# atmega_darlington_diodes.net
KiCad netlist of a schematic drawn in Altium Designer
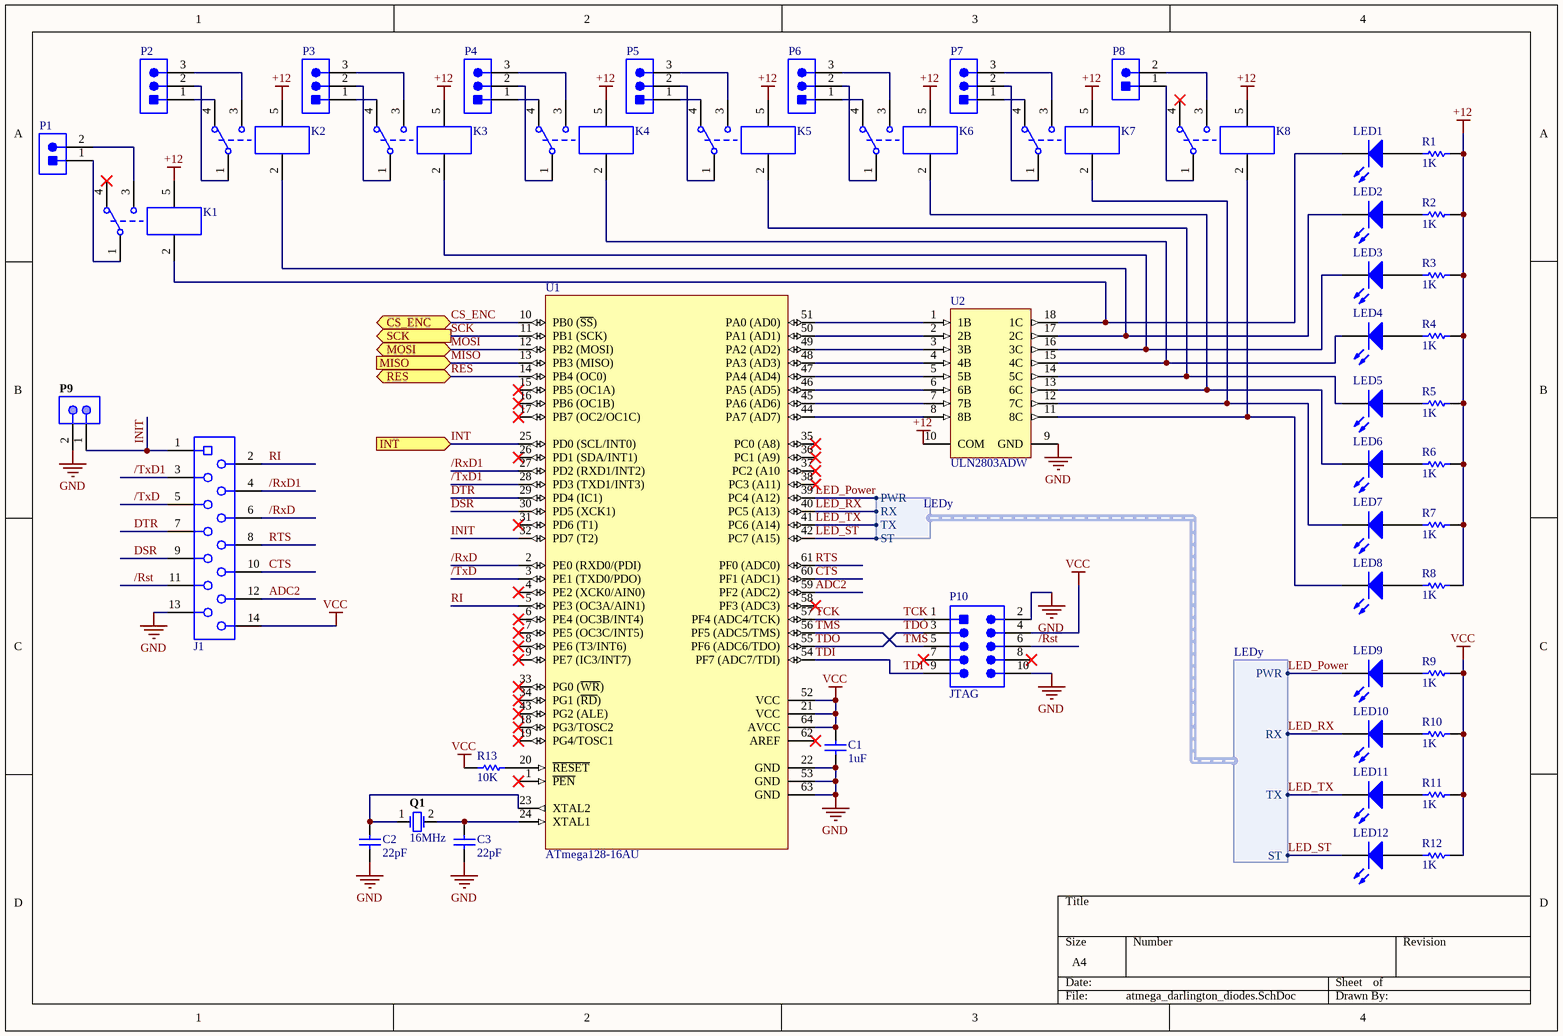
[diagram p0: atmega_darlington_diodes.SchDoc]

(export (version "E")
  (design (tool "Eeschema 10.0.6"))
  (components
    (comp (ref "C1")
      (value "1uF")
      (footprint "CAPC1206(3216)130_L")
      (description "CAP 1uF 10V ±5% 1206 (3216 Metric) Thickness 1.3mm SMD")
      (fields (field (name "TOLERANCE") "Â±5%"))
      (libsource (lib "Altium Content Vault") (part "CAP"))
    )
    (comp (ref "C2")
      (value "22pF")
      (footprint "CAPC1206(3216)100_L")
      (description "CAP 22pF 10V ±0.25pF 1206 (3216 Metric) Thickness 1mm SMD")
      (fields (field (name "TOLERANCE") "Â±0.25pF"))
      (libsource (lib "Altium Content Vault") (part "CAP"))
    )
    (comp (ref "C3")
      (value "22pF")
      (footprint "CAPC1206(3216)100_L")
      (description "CAP 22pF 10V ±0.25pF 1206 (3216 Metric) Thickness 1mm SMD")
      (fields (field (name "TOLERANCE") "Â±0.25pF"))
      (libsource (lib "Altium Content Vault") (part "CAP"))
    )
    (comp (ref "J1")
      (value "490107671412")
      (footprint "490107671412")
      (description "REDFIT IDC SKEDD Connector WR-WST, pitch 2.54 mm, 14 pins")
      (fields (field (name "MANUFACTURER") "Wurth Elektronik") (field (name "PUBLISHER") "WurthElektronik"))
      (libsource (lib "Altium Content Vault") (part "WE-CN-2S-F-R14"))
    )
    (comp (ref "K1")
      (value "JS1-12V")
      (footprint "PNSC-JS1-12V_V")
      (description "Cubic Type 1C Power Relay, SPDT, 10 A, 12 V, -40 to 70 degC, 5-Pin THD, RoHS, Bulk")
      (fields (field (name "MANUFACTURER") "Panasonic") (field (name "APPROVAL BODIES") "UL&CSA,TUV"))
      (libsource (lib "Altium Content Vault") (part "RELAY-SPDT-5_E"))
    )
    (comp (ref "K2")
      (value "JS1-12V")
      (footprint "PNSC-JS1-12V_V")
      (description "Cubic Type 1C Power Relay, SPDT, 10 A, 12 V, -40 to 70 degC, 5-Pin THD, RoHS, Bulk")
      (fields (field (name "MANUFACTURER") "Panasonic") (field (name "APPROVAL BODIES") "UL&CSA,TUV"))
      (libsource (lib "Altium Content Vault") (part "RELAY-SPDT-5_E"))
    )
    (comp (ref "K3")
      (value "JS1-12V")
      (footprint "PNSC-JS1-12V_V")
      (description "Cubic Type 1C Power Relay, SPDT, 10 A, 12 V, -40 to 70 degC, 5-Pin THD, RoHS, Bulk")
      (fields (field (name "MANUFACTURER") "Panasonic") (field (name "APPROVAL BODIES") "UL&CSA,TUV"))
      (libsource (lib "Altium Content Vault") (part "RELAY-SPDT-5_E"))
    )
    (comp (ref "K4")
      (value "JS1-12V")
      (footprint "PNSC-JS1-12V_V")
      (description "Cubic Type 1C Power Relay, SPDT, 10 A, 12 V, -40 to 70 degC, 5-Pin THD, RoHS, Bulk")
      (fields (field (name "MANUFACTURER") "Panasonic") (field (name "APPROVAL BODIES") "UL&CSA,TUV"))
      (libsource (lib "Altium Content Vault") (part "RELAY-SPDT-5_E"))
    )
    (comp (ref "K5")
      (value "JS1-12V")
      (footprint "PNSC-JS1-12V_V")
      (description "Cubic Type 1C Power Relay, SPDT, 10 A, 12 V, -40 to 70 degC, 5-Pin THD, RoHS, Bulk")
      (fields (field (name "MANUFACTURER") "Panasonic") (field (name "APPROVAL BODIES") "UL&CSA,TUV"))
      (libsource (lib "Altium Content Vault") (part "RELAY-SPDT-5_E"))
    )
    (comp (ref "K6")
      (value "JS1-12V")
      (footprint "PNSC-JS1-12V_V")
      (description "Cubic Type 1C Power Relay, SPDT, 10 A, 12 V, -40 to 70 degC, 5-Pin THD, RoHS, Bulk")
      (fields (field (name "MANUFACTURER") "Panasonic") (field (name "APPROVAL BODIES") "UL&CSA,TUV"))
      (libsource (lib "Altium Content Vault") (part "RELAY-SPDT-5_E"))
    )
    (comp (ref "K7")
      (value "JS1-12V")
      (footprint "PNSC-JS1-12V_V")
      (description "Cubic Type 1C Power Relay, SPDT, 10 A, 12 V, -40 to 70 degC, 5-Pin THD, RoHS, Bulk")
      (fields (field (name "MANUFACTURER") "Panasonic") (field (name "APPROVAL BODIES") "UL&CSA,TUV"))
      (libsource (lib "Altium Content Vault") (part "RELAY-SPDT-5_E"))
    )
    (comp (ref "K8")
      (value "JS1-12V")
      (footprint "PNSC-JS1-12V_V")
      (description "Cubic Type 1C Power Relay, SPDT, 10 A, 12 V, -40 to 70 degC, 5-Pin THD, RoHS, Bulk")
      (fields (field (name "MANUFACTURER") "Panasonic") (field (name "APPROVAL BODIES") "UL&CSA,TUV"))
      (libsource (lib "Altium Content Vault") (part "RELAY-SPDT-5_E"))
    )
    (comp (ref "LED1")
      (value "150120YS75000")
      (footprint "1206_A")
      (description "SMD mono-color Chip LED, WL-SMCW, Yellow")
      (fields (field (name "MANUFACTURER") "Wuerth Elektronik"))
      (libsource (lib "Altium Content Vault") (part "WE-LED_K1A2-2"))
    )
    (comp (ref "LED2")
      (value "150120YS75000")
      (footprint "1206_A")
      (description "SMD mono-color Chip LED, WL-SMCW, Yellow")
      (fields (field (name "MANUFACTURER") "Wuerth Elektronik"))
      (libsource (lib "Altium Content Vault") (part "WE-LED_K1A2-2"))
    )
    (comp (ref "LED3")
      (value "150120YS75000")
      (footprint "1206_A")
      (description "SMD mono-color Chip LED, WL-SMCW, Yellow")
      (fields (field (name "MANUFACTURER") "Wuerth Elektronik"))
      (libsource (lib "Altium Content Vault") (part "WE-LED_K1A2-2"))
    )
    (comp (ref "LED4")
      (value "150120YS75000")
      (footprint "1206_A")
      (description "SMD mono-color Chip LED, WL-SMCW, Yellow")
      (fields (field (name "MANUFACTURER") "Wuerth Elektronik"))
      (libsource (lib "Altium Content Vault") (part "WE-LED_K1A2-2"))
    )
    (comp (ref "LED5")
      (value "150120YS75000")
      (footprint "1206_A")
      (description "SMD mono-color Chip LED, WL-SMCW, Yellow")
      (fields (field (name "MANUFACTURER") "Wuerth Elektronik"))
      (libsource (lib "Altium Content Vault") (part "WE-LED_K1A2-2"))
    )
    (comp (ref "LED6")
      (value "150120YS75000")
      (footprint "1206_A")
      (description "SMD mono-color Chip LED, WL-SMCW, Yellow")
      (fields (field (name "MANUFACTURER") "Wuerth Elektronik"))
      (libsource (lib "Altium Content Vault") (part "WE-LED_K1A2-2"))
    )
    (comp (ref "LED7")
      (value "150120YS75000")
      (footprint "1206_A")
      (description "SMD mono-color Chip LED, WL-SMCW, Yellow")
      (fields (field (name "MANUFACTURER") "Wuerth Elektronik"))
      (libsource (lib "Altium Content Vault") (part "WE-LED_K1A2-2"))
    )
    (comp (ref "LED8")
      (value "150120YS75000")
      (footprint "1206_A")
      (description "SMD mono-color Chip LED, WL-SMCW, Yellow")
      (fields (field (name "MANUFACTURER") "Wuerth Elektronik"))
      (libsource (lib "Altium Content Vault") (part "WE-LED_K1A2-2"))
    )
    (comp (ref "LED9")
      (value "150120BS75000")
      (footprint "1206_A")
      (description "SMD mono-color Chip LED, WL-SMCW, Blue")
      (fields (field (name "MANUFACTURER") "Wuerth Elektronik"))
      (libsource (lib "Altium Content Vault") (part "WE-LED_K1A2-2"))
    )
    (comp (ref "LED10")
      (value "150120GS75000")
      (footprint "1206_A")
      (description "SMD mono-color Chip LED, WL-SMCW, Green")
      (fields (field (name "MANUFACTURER") "Wuerth Elektronik"))
      (libsource (lib "Altium Content Vault") (part "WE-LED_K1A2-2"))
    )
    (comp (ref "LED11")
      (value "150120YS75000")
      (footprint "1206_A")
      (description "SMD mono-color Chip LED, WL-SMCW, Yellow")
      (fields (field (name "MANUFACTURER") "Wuerth Elektronik"))
      (libsource (lib "Altium Content Vault") (part "WE-LED_K1A2-2"))
    )
    (comp (ref "LED12")
      (value "150120RS75000")
      (footprint "1206_A")
      (description "SMD mono-color Chip LED, WL-SMCW, Red")
      (fields (field (name "MANUFACTURER") "Wuerth Elektronik"))
      (libsource (lib "Altium Content Vault") (part "WE-LED_K1A2-2"))
    )
    (comp (ref "P1")
      (value "SCREW-5.0/5.08 2WAYS")
      (footprint "SCREW-5.0-2WAYS_V")
      (description "Socket, Screw Terminal Block, 2 Way, 5.0 mm Pitch, 90 Degree Angle, Through-Hole")
      (fields (field (name "MANUFACTURER") "No Vendor"))
      (libsource (lib "Altium Content Vault") (part "SCREW-2WAYS"))
    )
    (comp (ref "P2")
      (value "SCREW-5.0/5.08 3WAYS")
      (footprint "SCREW-5.0-3WAYS_V")
      (description "Socket, Screw Terminal Block, 3 Way, 5.0 mm Pitch, 90 Degree Angle, Through-Hole")
      (fields (field (name "MANUFACTURER") "No Vendor"))
      (libsource (lib "Altium Content Vault") (part "SCREW-3WAYS"))
    )
    (comp (ref "P3")
      (value "SCREW-5.0/5.08 3WAYS")
      (footprint "SCREW-5.0-3WAYS_V")
      (description "Socket, Screw Terminal Block, 3 Way, 5.0 mm Pitch, 90 Degree Angle, Through-Hole")
      (fields (field (name "MANUFACTURER") "No Vendor"))
      (libsource (lib "Altium Content Vault") (part "SCREW-3WAYS"))
    )
    (comp (ref "P4")
      (value "SCREW-5.0/5.08 3WAYS")
      (footprint "SCREW-5.0-3WAYS_V")
      (description "Socket, Screw Terminal Block, 3 Way, 5.0 mm Pitch, 90 Degree Angle, Through-Hole")
      (fields (field (name "MANUFACTURER") "No Vendor"))
      (libsource (lib "Altium Content Vault") (part "SCREW-3WAYS"))
    )
    (comp (ref "P5")
      (value "SCREW-5.0/5.08 3WAYS")
      (footprint "SCREW-5.0-3WAYS_V")
      (description "Socket, Screw Terminal Block, 3 Way, 5.0 mm Pitch, 90 Degree Angle, Through-Hole")
      (fields (field (name "MANUFACTURER") "No Vendor"))
      (libsource (lib "Altium Content Vault") (part "SCREW-3WAYS"))
    )
    (comp (ref "P6")
      (value "SCREW-5.0/5.08 3WAYS")
      (footprint "SCREW-5.0-3WAYS_V")
      (description "Socket, Screw Terminal Block, 3 Way, 5.0 mm Pitch, 90 Degree Angle, Through-Hole")
      (fields (field (name "MANUFACTURER") "No Vendor"))
      (libsource (lib "Altium Content Vault") (part "SCREW-3WAYS"))
    )
    (comp (ref "P7")
      (value "SCREW-5.0/5.08 3WAYS")
      (footprint "SCREW-5.0-3WAYS_V")
      (description "Socket, Screw Terminal Block, 3 Way, 5.0 mm Pitch, 90 Degree Angle, Through-Hole")
      (fields (field (name "MANUFACTURER") "No Vendor"))
      (libsource (lib "Altium Content Vault") (part "SCREW-3WAYS"))
    )
    (comp (ref "P8")
      (value "SCREW-5.0/5.08 2WAYS")
      (footprint "SCREW-5.0-2WAYS_V")
      (description "Socket, Screw Terminal Block, 2 Way, 5.0 mm Pitch, 90 Degree Angle, Through-Hole")
      (fields (field (name "MANUFACTURER") "No Vendor"))
      (libsource (lib "Altium Content Vault") (part "SCREW-2WAYS"))
    )
    (comp (ref "P9")
      (value "PH2541-2-SPGRH-6-3")
      (footprint "PH2541-2-SPGRH-6-3_V")
      (description "Male Header, Pitch 2.54mm, 2x1 Position, Mated Height 6mm, Tail Length 3mm")
      (libsource (lib "Altium Content Vault") (part "PCE-HDR-1P-M-R2"))
    )
    (comp (ref "P10")
      (value "JTAG")
      (footprint "3M-2510-6002_V")
      (fields (field (name "MANUFACTURER") "3M"))
      (libsource (lib "Altium Content Vault") (part "CN-2P-M-R10"))
    )
    (comp (ref "Q1")
      (value "16MHz")
      (footprint "JPY-HC-49US")
      (description "Crystal, 16 MHz, +/- 30 ppm, 18 pF, -20 to 70 degC, 2-Pin THD")
      (fields (field (name "MANUFACTURER") "Jing peng yuan"))
      (libsource (lib "Altium Content Vault") (part "XTAL-1-2-2"))
    )
    (comp (ref "R1")
      (value "1K")
      (footprint "RESC1206(3216)_L")
      (description "1K 0.25W 1% 1206 (3216 Metric)  SMD")
      (fields (field (name "POWER") "0.25 W") (field (name "TOLERANCE") "1 %"))
      (libsource (lib "Altium Content Vault") (part "RES"))
    )
    (comp (ref "R2")
      (value "1K")
      (footprint "RESC1206(3216)_L")
      (description "1K 0.25W 1% 1206 (3216 Metric)  SMD")
      (fields (field (name "POWER") "0.25 W") (field (name "TOLERANCE") "1 %"))
      (libsource (lib "Altium Content Vault") (part "RES"))
    )
    (comp (ref "R3")
      (value "1K")
      (footprint "RESC1206(3216)_L")
      (description "1K 0.25W 1% 1206 (3216 Metric)  SMD")
      (fields (field (name "POWER") "0.25 W") (field (name "TOLERANCE") "1 %"))
      (libsource (lib "Altium Content Vault") (part "RES"))
    )
    (comp (ref "R4")
      (value "1K")
      (footprint "RESC1206(3216)_L")
      (description "1K 0.25W 1% 1206 (3216 Metric)  SMD")
      (fields (field (name "POWER") "0.25 W") (field (name "TOLERANCE") "1 %"))
      (libsource (lib "Altium Content Vault") (part "RES"))
    )
    (comp (ref "R5")
      (value "1K")
      (footprint "RESC1206(3216)_L")
      (description "1K 0.25W 1% 1206 (3216 Metric)  SMD")
      (fields (field (name "POWER") "0.25 W") (field (name "TOLERANCE") "1 %"))
      (libsource (lib "Altium Content Vault") (part "RES"))
    )
    (comp (ref "R6")
      (value "1K")
      (footprint "RESC1206(3216)_L")
      (description "1K 0.25W 1% 1206 (3216 Metric)  SMD")
      (fields (field (name "POWER") "0.25 W") (field (name "TOLERANCE") "1 %"))
      (libsource (lib "Altium Content Vault") (part "RES"))
    )
    (comp (ref "R7")
      (value "1K")
      (footprint "RESC1206(3216)_L")
      (description "1K 0.25W 1% 1206 (3216 Metric)  SMD")
      (fields (field (name "POWER") "0.25 W") (field (name "TOLERANCE") "1 %"))
      (libsource (lib "Altium Content Vault") (part "RES"))
    )
    (comp (ref "R8")
      (value "1K")
      (footprint "RESC1206(3216)_L")
      (description "1K 0.25W 1% 1206 (3216 Metric)  SMD")
      (fields (field (name "POWER") "0.25 W") (field (name "TOLERANCE") "1 %"))
      (libsource (lib "Altium Content Vault") (part "RES"))
    )
    (comp (ref "R9")
      (value "1K")
      (footprint "RESC1206(3216)_L")
      (description "1K 0.25W 1% 1206 (3216 Metric)  SMD")
      (fields (field (name "POWER") "0.25 W") (field (name "TOLERANCE") "1 %"))
      (libsource (lib "Altium Content Vault") (part "RES"))
    )
    (comp (ref "R10")
      (value "1K")
      (footprint "RESC1206(3216)_L")
      (description "1K 0.25W 1% 1206 (3216 Metric)  SMD")
      (fields (field (name "POWER") "0.25 W") (field (name "TOLERANCE") "1 %"))
      (libsource (lib "Altium Content Vault") (part "RES"))
    )
    (comp (ref "R11")
      (value "1K")
      (footprint "RESC1206(3216)_L")
      (description "1K 0.25W 1% 1206 (3216 Metric)  SMD")
      (fields (field (name "POWER") "0.25 W") (field (name "TOLERANCE") "1 %"))
      (libsource (lib "Altium Content Vault") (part "RES"))
    )
    (comp (ref "R12")
      (value "1K")
      (footprint "RESC1206(3216)_L")
      (description "1K 0.25W 1% 1206 (3216 Metric)  SMD")
      (fields (field (name "POWER") "0.25 W") (field (name "TOLERANCE") "1 %"))
      (libsource (lib "Altium Content Vault") (part "RES"))
    )
    (comp (ref "R13")
      (value "10K")
      (footprint "RESC1206(3216)_L")
      (description "10K 0.25W 1% 1206 (3216 Metric)  SMD")
      (fields (field (name "POWER") "0.25 W") (field (name "TOLERANCE") "1 %"))
      (libsource (lib "Altium Content Vault") (part "RES"))
    )
    (comp (ref "U1")
      (value "ATmega128-16AU")
      (footprint "64A_L")
      (libsource (lib "Altium Content Vault") (part "MC-8B-AT64-SQ64"))
    )
    (comp (ref "U2")
      (value "ULN2803ADW")
      (footprint "DW0018A_L")
      (fields (field (name "MANUFACTURER") "Texas Instruments"))
      (libsource (lib "Altium Content Vault") (part "TI-ULN2803A-SOIC_DW-18"))
    )
  )
  (nets
    (net (code "2") (name "+12") (class "Default")
      (node (ref "K1") (pin "5") (pinfunction "5_5") (pintype "passive"))
      (node (ref "K2") (pin "5") (pinfunction "5_5") (pintype "passive"))
      (node (ref "K3") (pin "5") (pinfunction "5_5") (pintype "passive"))
      (node (ref "K4") (pin "5") (pinfunction "5_5") (pintype "passive"))
      (node (ref "K5") (pin "5") (pinfunction "5_5") (pintype "passive"))
      (node (ref "K6") (pin "5") (pinfunction "5_5") (pintype "passive"))
      (node (ref "K7") (pin "5") (pinfunction "5_5") (pintype "passive"))
      (node (ref "K8") (pin "5") (pinfunction "5_5") (pintype "passive"))
      (node (ref "R1") (pin "2") (pinfunction "2_2") (pintype "passive"))
      (node (ref "R2") (pin "2") (pinfunction "2_2") (pintype "passive"))
      (node (ref "R3") (pin "2") (pinfunction "2_2") (pintype "passive"))
      (node (ref "R4") (pin "2") (pinfunction "2_2") (pintype "passive"))
      (node (ref "R5") (pin "2") (pinfunction "2_2") (pintype "passive"))
      (node (ref "R6") (pin "2") (pinfunction "2_2") (pintype "passive"))
      (node (ref "R7") (pin "2") (pinfunction "2_2") (pintype "passive"))
      (node (ref "R8") (pin "2") (pinfunction "2_2") (pintype "passive"))
      (node (ref "U2") (pin "10") (pinfunction "COM_10") (pintype "passive"))
    )
    (net (code "3") (name "/ADC2") (class "Default")
      (node (ref "J1") (pin "12") (pinfunction "12_12") (pintype "passive"))
      (node (ref "U1") (pin "59") (pinfunction "PF2_(ADC2)_59") (pintype "bidirectional"))
    )
    (net (code "4") (name "/CS_ENC") (class "Default")
      (node (ref "U1") (pin "10") (pinfunction "PB0_(~{SS})_10") (pintype "bidirectional"))
    )
    (net (code "5") (name "/CTS") (class "Default")
      (node (ref "J1") (pin "10") (pinfunction "10_10") (pintype "passive"))
      (node (ref "U1") (pin "60") (pinfunction "PF1_(ADC1)_60") (pintype "bidirectional"))
    )
    (net (code "6") (name "/DSR") (class "Default")
      (node (ref "J1") (pin "9") (pinfunction "9_9") (pintype "passive"))
      (node (ref "U1") (pin "30") (pinfunction "PD5_(XCK1)_30") (pintype "bidirectional"))
    )
    (net (code "7") (name "/DTR") (class "Default")
      (node (ref "J1") (pin "7") (pinfunction "7_7") (pintype "passive"))
      (node (ref "U1") (pin "29") (pinfunction "PD4_(IC1)_29") (pintype "bidirectional"))
    )
    (net (code "8") (name "/INIT") (class "Default")
      (node (ref "J1") (pin "1") (pinfunction "1_1") (pintype "passive"))
      (node (ref "P9") (pin "1") (pinfunction "1_1") (pintype "passive"))
      (node (ref "U1") (pin "32") (pinfunction "PD7_(T2)_32") (pintype "bidirectional"))
    )
    (net (code "9") (name "/INT") (class "Default")
      (node (ref "U1") (pin "25") (pinfunction "PD0_(SCL/INT0)_25") (pintype "bidirectional"))
    )
    (net (code "10") (name "/LED_Power") (class "Default")
      (node (ref "LED9") (pin "1") (pinfunction "K_1") (pintype "passive"))
      (node (ref "U1") (pin "39") (pinfunction "PC4_(A12)_39") (pintype "bidirectional"))
    )
    (net (code "11") (name "/LED_RX") (class "Default")
      (node (ref "LED10") (pin "1") (pinfunction "K_1") (pintype "passive"))
      (node (ref "U1") (pin "40") (pinfunction "PC5_(A13)_40") (pintype "bidirectional"))
    )
    (net (code "12") (name "/LED_ST") (class "Default")
      (node (ref "LED12") (pin "1") (pinfunction "K_1") (pintype "passive"))
      (node (ref "U1") (pin "42") (pinfunction "PC7_(A15)_42") (pintype "bidirectional"))
    )
    (net (code "13") (name "/LED_TX") (class "Default")
      (node (ref "LED11") (pin "1") (pinfunction "K_1") (pintype "passive"))
      (node (ref "U1") (pin "41") (pinfunction "PC6_(A14)_41") (pintype "bidirectional"))
    )
    (net (code "14") (name "/MISO") (class "Default")
      (node (ref "U1") (pin "13") (pinfunction "PB3_(MISO)_13") (pintype "bidirectional"))
    )
    (net (code "15") (name "/MOSI") (class "Default")
      (node (ref "U1") (pin "12") (pinfunction "PB2_(MOSI)_12") (pintype "bidirectional"))
    )
    (net (code "16") (name "/RES") (class "Default")
      (node (ref "U1") (pin "14") (pinfunction "PB4_(OC0)_14") (pintype "bidirectional"))
    )
    (net (code "17") (name "/RI") (class "Default")
      (node (ref "J1") (pin "2") (pinfunction "2_2") (pintype "passive"))
      (node (ref "U1") (pin "5") (pinfunction "PE3_(OC3A/AIN1)_5") (pintype "bidirectional"))
    )
    (net (code "18") (name "/RTS") (class "Default")
      (node (ref "J1") (pin "8") (pinfunction "8_8") (pintype "passive"))
      (node (ref "U1") (pin "61") (pinfunction "PF0_(ADC0)_61") (pintype "bidirectional"))
    )
    (net (code "19") (name "/SCK") (class "Default")
      (node (ref "U1") (pin "11") (pinfunction "PB1_(SCK)_11") (pintype "bidirectional"))
    )
    (net (code "20") (name "/TCK") (class "Default")
      (node (ref "P10") (pin "1") (pinfunction "1_1") (pintype "passive"))
      (node (ref "U1") (pin "57") (pinfunction "PF4_(ADC4/TCK)_57") (pintype "bidirectional"))
    )
    (net (code "21") (name "/TDI") (class "Default")
      (node (ref "P10") (pin "9") (pinfunction "9_9") (pintype "passive"))
      (node (ref "U1") (pin "54") (pinfunction "PF7_(ADC7/TDI)_54") (pintype "bidirectional"))
    )
    (net (code "22") (name "/TDO") (class "Default")
      (node (ref "P10") (pin "3") (pinfunction "3_3") (pintype "passive"))
      (node (ref "U1") (pin "55") (pinfunction "PF6_(ADC6/TDO)_55") (pintype "bidirectional"))
    )
    (net (code "23") (name "/TMS") (class "Default")
      (node (ref "P10") (pin "5") (pinfunction "5_5") (pintype "passive"))
      (node (ref "U1") (pin "56") (pinfunction "PF5_(ADC5/TMS)_56") (pintype "bidirectional"))
    )
    (net (code "25") (name "/{slash}Rst") (class "Default")
      (node (ref "J1") (pin "11") (pinfunction "11_11") (pintype "passive"))
      (node (ref "P10") (pin "6") (pinfunction "6_6") (pintype "passive"))
    )
    (net (code "26") (name "/{slash}RxD") (class "Default")
      (node (ref "J1") (pin "6") (pinfunction "6_6") (pintype "passive"))
      (node (ref "U1") (pin "2") (pinfunction "PE0_(RXD0/(PDI)_2") (pintype "bidirectional"))
    )
    (net (code "27") (name "/{slash}RxD1") (class "Default")
      (node (ref "J1") (pin "4") (pinfunction "4_4") (pintype "passive"))
      (node (ref "U1") (pin "27") (pinfunction "PD2_(RXD1/INT2)_27") (pintype "bidirectional"))
    )
    (net (code "28") (name "/{slash}TxD") (class "Default")
      (node (ref "J1") (pin "5") (pinfunction "5_5") (pintype "passive"))
      (node (ref "U1") (pin "3") (pinfunction "PE1_(TXD0/PDO)_3") (pintype "bidirectional"))
    )
    (net (code "29") (name "/{slash}TxD1") (class "Default")
      (node (ref "J1") (pin "3") (pinfunction "3_3") (pintype "passive"))
      (node (ref "U1") (pin "28") (pinfunction "PD3_(TXD1/INT3)_28") (pintype "bidirectional"))
    )
    (net (code "30") (name "GND") (class "Default")
      (node (ref "C1") (pin "1") (pinfunction "1_1") (pintype "passive"))
      (node (ref "C2") (pin "1") (pinfunction "1_1") (pintype "passive"))
      (node (ref "C3") (pin "1") (pinfunction "1_1") (pintype "passive"))
      (node (ref "J1") (pin "13") (pinfunction "13_13") (pintype "passive"))
      (node (ref "P10") (pin "10") (pinfunction "10_10") (pintype "passive"))
      (node (ref "P10") (pin "2") (pinfunction "2_2") (pintype "passive"))
      (node (ref "P9") (pin "2") (pinfunction "2_2") (pintype "passive"))
      (node (ref "U1") (pin "22") (pinfunction "GND_22") (pintype "power_in"))
      (node (ref "U1") (pin "53") (pinfunction "GND_53") (pintype "power_in"))
      (node (ref "U1") (pin "63") (pinfunction "GND_63") (pintype "power_in"))
      (node (ref "U2") (pin "9") (pinfunction "GND_9") (pintype "power_in"))
    )
    (net (code "31") (name "Net-(K1-COM)") (class "Default")
      (node (ref "K1") (pin "1") (pinfunction "COM_1") (pintype "passive"))
      (node (ref "P1") (pin "1") (pinfunction "1_1") (pintype "passive"))
    )
    (net (code "32") (name "Net-(K1-N.O.)") (class "Default")
      (node (ref "K1") (pin "3") (pinfunction "N.O._3") (pintype "passive"))
      (node (ref "P1") (pin "2") (pinfunction "2_2") (pintype "passive"))
    )
    (net (code "33") (name "Net-(K2-COM)") (class "Default")
      (node (ref "K2") (pin "1") (pinfunction "COM_1") (pintype "passive"))
      (node (ref "P2") (pin "2") (pinfunction "2_2") (pintype "passive"))
    )
    (net (code "34") (name "Net-(K2-N.C.)") (class "Default")
      (node (ref "K2") (pin "4") (pinfunction "N.C._4") (pintype "passive"))
      (node (ref "P2") (pin "1") (pinfunction "1_1") (pintype "passive"))
    )
    (net (code "35") (name "Net-(K2-N.O.)") (class "Default")
      (node (ref "K2") (pin "3") (pinfunction "N.O._3") (pintype "passive"))
      (node (ref "P2") (pin "3") (pinfunction "3_3") (pintype "passive"))
    )
    (net (code "36") (name "Net-(K3-COM)") (class "Default")
      (node (ref "K3") (pin "1") (pinfunction "COM_1") (pintype "passive"))
      (node (ref "P3") (pin "2") (pinfunction "2_2") (pintype "passive"))
    )
    (net (code "37") (name "Net-(K3-N.C.)") (class "Default")
      (node (ref "K3") (pin "4") (pinfunction "N.C._4") (pintype "passive"))
      (node (ref "P3") (pin "1") (pinfunction "1_1") (pintype "passive"))
    )
    (net (code "38") (name "Net-(K3-N.O.)") (class "Default")
      (node (ref "K3") (pin "3") (pinfunction "N.O._3") (pintype "passive"))
      (node (ref "P3") (pin "3") (pinfunction "3_3") (pintype "passive"))
    )
    (net (code "39") (name "Net-(K4-COM)") (class "Default")
      (node (ref "K4") (pin "1") (pinfunction "COM_1") (pintype "passive"))
      (node (ref "P4") (pin "2") (pinfunction "2_2") (pintype "passive"))
    )
    (net (code "40") (name "Net-(K4-N.C.)") (class "Default")
      (node (ref "K4") (pin "4") (pinfunction "N.C._4") (pintype "passive"))
      (node (ref "P4") (pin "1") (pinfunction "1_1") (pintype "passive"))
    )
    (net (code "41") (name "Net-(K4-N.O.)") (class "Default")
      (node (ref "K4") (pin "3") (pinfunction "N.O._3") (pintype "passive"))
      (node (ref "P4") (pin "3") (pinfunction "3_3") (pintype "passive"))
    )
    (net (code "42") (name "Net-(K5-COM)") (class "Default")
      (node (ref "K5") (pin "1") (pinfunction "COM_1") (pintype "passive"))
      (node (ref "P5") (pin "2") (pinfunction "2_2") (pintype "passive"))
    )
    (net (code "43") (name "Net-(K5-N.C.)") (class "Default")
      (node (ref "K5") (pin "4") (pinfunction "N.C._4") (pintype "passive"))
      (node (ref "P5") (pin "1") (pinfunction "1_1") (pintype "passive"))
    )
    (net (code "44") (name "Net-(K5-N.O.)") (class "Default")
      (node (ref "K5") (pin "3") (pinfunction "N.O._3") (pintype "passive"))
      (node (ref "P5") (pin "3") (pinfunction "3_3") (pintype "passive"))
    )
    (net (code "45") (name "Net-(K6-COM)") (class "Default")
      (node (ref "K6") (pin "1") (pinfunction "COM_1") (pintype "passive"))
      (node (ref "P6") (pin "2") (pinfunction "2_2") (pintype "passive"))
    )
    (net (code "46") (name "Net-(K6-N.C.)") (class "Default")
      (node (ref "K6") (pin "4") (pinfunction "N.C._4") (pintype "passive"))
      (node (ref "P6") (pin "1") (pinfunction "1_1") (pintype "passive"))
    )
    (net (code "47") (name "Net-(K6-N.O.)") (class "Default")
      (node (ref "K6") (pin "3") (pinfunction "N.O._3") (pintype "passive"))
      (node (ref "P6") (pin "3") (pinfunction "3_3") (pintype "passive"))
    )
    (net (code "48") (name "Net-(K7-COM)") (class "Default")
      (node (ref "K7") (pin "1") (pinfunction "COM_1") (pintype "passive"))
      (node (ref "P7") (pin "2") (pinfunction "2_2") (pintype "passive"))
    )
    (net (code "49") (name "Net-(K7-N.C.)") (class "Default")
      (node (ref "K7") (pin "4") (pinfunction "N.C._4") (pintype "passive"))
      (node (ref "P7") (pin "1") (pinfunction "1_1") (pintype "passive"))
    )
    (net (code "50") (name "Net-(K7-N.O.)") (class "Default")
      (node (ref "K7") (pin "3") (pinfunction "N.O._3") (pintype "passive"))
      (node (ref "P7") (pin "3") (pinfunction "3_3") (pintype "passive"))
    )
    (net (code "51") (name "Net-(K8-COM)") (class "Default")
      (node (ref "K8") (pin "1") (pinfunction "COM_1") (pintype "passive"))
      (node (ref "P8") (pin "1") (pinfunction "1_1") (pintype "passive"))
    )
    (net (code "52") (name "Net-(K8-N.O.)") (class "Default")
      (node (ref "K8") (pin "3") (pinfunction "N.O._3") (pintype "passive"))
      (node (ref "P8") (pin "2") (pinfunction "2_2") (pintype "passive"))
    )
    (net (code "53") (name "Net-(LED1-A)") (class "Default")
      (node (ref "LED1") (pin "2") (pinfunction "A_2") (pintype "passive"))
      (node (ref "R1") (pin "1") (pinfunction "1_1") (pintype "passive"))
    )
    (net (code "54") (name "Net-(LED1-K)") (class "Default")
      (node (ref "K1") (pin "2") (pinfunction "2_2") (pintype "passive"))
      (node (ref "LED1") (pin "1") (pinfunction "K_1") (pintype "passive"))
      (node (ref "U2") (pin "18") (pinfunction "1C_18") (pintype "output"))
    )
    (net (code "55") (name "Net-(LED2-A)") (class "Default")
      (node (ref "LED2") (pin "2") (pinfunction "A_2") (pintype "passive"))
      (node (ref "R2") (pin "1") (pinfunction "1_1") (pintype "passive"))
    )
    (net (code "56") (name "Net-(LED2-K)") (class "Default")
      (node (ref "K2") (pin "2") (pinfunction "2_2") (pintype "passive"))
      (node (ref "LED2") (pin "1") (pinfunction "K_1") (pintype "passive"))
      (node (ref "U2") (pin "17") (pinfunction "2C_17") (pintype "output"))
    )
    (net (code "57") (name "Net-(LED3-A)") (class "Default")
      (node (ref "LED3") (pin "2") (pinfunction "A_2") (pintype "passive"))
      (node (ref "R3") (pin "1") (pinfunction "1_1") (pintype "passive"))
    )
    (net (code "58") (name "Net-(LED3-K)") (class "Default")
      (node (ref "K3") (pin "2") (pinfunction "2_2") (pintype "passive"))
      (node (ref "LED3") (pin "1") (pinfunction "K_1") (pintype "passive"))
      (node (ref "U2") (pin "16") (pinfunction "3C_16") (pintype "output"))
    )
    (net (code "59") (name "Net-(LED4-A)") (class "Default")
      (node (ref "LED4") (pin "2") (pinfunction "A_2") (pintype "passive"))
      (node (ref "R4") (pin "1") (pinfunction "1_1") (pintype "passive"))
    )
    (net (code "60") (name "Net-(LED4-K)") (class "Default")
      (node (ref "K4") (pin "2") (pinfunction "2_2") (pintype "passive"))
      (node (ref "LED4") (pin "1") (pinfunction "K_1") (pintype "passive"))
      (node (ref "U2") (pin "15") (pinfunction "4C_15") (pintype "output"))
    )
    (net (code "61") (name "Net-(LED5-A)") (class "Default")
      (node (ref "LED5") (pin "2") (pinfunction "A_2") (pintype "passive"))
      (node (ref "R5") (pin "1") (pinfunction "1_1") (pintype "passive"))
    )
    (net (code "62") (name "Net-(LED5-K)") (class "Default")
      (node (ref "K5") (pin "2") (pinfunction "2_2") (pintype "passive"))
      (node (ref "LED5") (pin "1") (pinfunction "K_1") (pintype "passive"))
      (node (ref "U2") (pin "14") (pinfunction "5C_14") (pintype "output"))
    )
    (net (code "63") (name "Net-(LED6-A)") (class "Default")
      (node (ref "LED6") (pin "2") (pinfunction "A_2") (pintype "passive"))
      (node (ref "R6") (pin "1") (pinfunction "1_1") (pintype "passive"))
    )
    (net (code "64") (name "Net-(LED6-K)") (class "Default")
      (node (ref "K6") (pin "2") (pinfunction "2_2") (pintype "passive"))
      (node (ref "LED6") (pin "1") (pinfunction "K_1") (pintype "passive"))
      (node (ref "U2") (pin "13") (pinfunction "6C_13") (pintype "output"))
    )
    (net (code "65") (name "Net-(LED7-A)") (class "Default")
      (node (ref "LED7") (pin "2") (pinfunction "A_2") (pintype "passive"))
      (node (ref "R7") (pin "1") (pinfunction "1_1") (pintype "passive"))
    )
    (net (code "66") (name "Net-(LED7-K)") (class "Default")
      (node (ref "K7") (pin "2") (pinfunction "2_2") (pintype "passive"))
      (node (ref "LED7") (pin "1") (pinfunction "K_1") (pintype "passive"))
      (node (ref "U2") (pin "12") (pinfunction "7C_12") (pintype "output"))
    )
    (net (code "67") (name "Net-(LED8-A)") (class "Default")
      (node (ref "LED8") (pin "2") (pinfunction "A_2") (pintype "passive"))
      (node (ref "R8") (pin "1") (pinfunction "1_1") (pintype "passive"))
    )
    (net (code "68") (name "Net-(LED8-K)") (class "Default")
      (node (ref "K8") (pin "2") (pinfunction "2_2") (pintype "passive"))
      (node (ref "LED8") (pin "1") (pinfunction "K_1") (pintype "passive"))
      (node (ref "U2") (pin "11") (pinfunction "8C_11") (pintype "output"))
    )
    (net (code "69") (name "Net-(LED9-A)") (class "Default")
      (node (ref "LED9") (pin "2") (pinfunction "A_2") (pintype "passive"))
      (node (ref "R9") (pin "1") (pinfunction "1_1") (pintype "passive"))
    )
    (net (code "70") (name "Net-(LED10-A)") (class "Default")
      (node (ref "LED10") (pin "2") (pinfunction "A_2") (pintype "passive"))
      (node (ref "R10") (pin "1") (pinfunction "1_1") (pintype "passive"))
    )
    (net (code "71") (name "Net-(LED11-A)") (class "Default")
      (node (ref "LED11") (pin "2") (pinfunction "A_2") (pintype "passive"))
      (node (ref "R11") (pin "1") (pinfunction "1_1") (pintype "passive"))
    )
    (net (code "72") (name "Net-(LED12-A)") (class "Default")
      (node (ref "LED12") (pin "2") (pinfunction "A_2") (pintype "passive"))
      (node (ref "R12") (pin "1") (pinfunction "1_1") (pintype "passive"))
    )
    (net (code "73") (name "Net-(U1-PA0_(AD0))") (class "Default")
      (node (ref "U1") (pin "51") (pinfunction "PA0_(AD0)_51") (pintype "bidirectional"))
      (node (ref "U2") (pin "1") (pinfunction "1B_1") (pintype "input"))
    )
    (net (code "74") (name "Net-(U1-PA1_(AD1))") (class "Default")
      (node (ref "U1") (pin "50") (pinfunction "PA1_(AD1)_50") (pintype "bidirectional"))
      (node (ref "U2") (pin "2") (pinfunction "2B_2") (pintype "input"))
    )
    (net (code "75") (name "Net-(U1-PA2_(AD2))") (class "Default")
      (node (ref "U1") (pin "49") (pinfunction "PA2_(AD2)_49") (pintype "bidirectional"))
      (node (ref "U2") (pin "3") (pinfunction "3B_3") (pintype "input"))
    )
    (net (code "76") (name "Net-(U1-PA3_(AD3))") (class "Default")
      (node (ref "U1") (pin "48") (pinfunction "PA3_(AD3)_48") (pintype "bidirectional"))
      (node (ref "U2") (pin "4") (pinfunction "4B_4") (pintype "input"))
    )
    (net (code "77") (name "Net-(U1-PA4_(AD4))") (class "Default")
      (node (ref "U1") (pin "47") (pinfunction "PA4_(AD4)_47") (pintype "bidirectional"))
      (node (ref "U2") (pin "5") (pinfunction "5B_5") (pintype "input"))
    )
    (net (code "78") (name "Net-(U1-PA5_(AD5))") (class "Default")
      (node (ref "U1") (pin "46") (pinfunction "PA5_(AD5)_46") (pintype "bidirectional"))
      (node (ref "U2") (pin "6") (pinfunction "6B_6") (pintype "input"))
    )
    (net (code "79") (name "Net-(U1-PA6_(AD6))") (class "Default")
      (node (ref "U1") (pin "45") (pinfunction "PA6_(AD6)_45") (pintype "bidirectional"))
      (node (ref "U2") (pin "7") (pinfunction "7B_7") (pintype "input"))
    )
    (net (code "80") (name "Net-(U1-PA7_(AD7))") (class "Default")
      (node (ref "U1") (pin "44") (pinfunction "PA7_(AD7)_44") (pintype "bidirectional"))
      (node (ref "U2") (pin "8") (pinfunction "8B_8") (pintype "input"))
    )
    (net (code "81") (name "Net-(U1-XTAL1)") (class "Default")
      (node (ref "C3") (pin "2") (pinfunction "2_2") (pintype "passive"))
      (node (ref "Q1") (pin "2") (pinfunction "2_2") (pintype "passive"))
      (node (ref "U1") (pin "24") (pinfunction "XTAL1_24") (pintype "input"))
    )
    (net (code "82") (name "Net-(U1-XTAL2)") (class "Default")
      (node (ref "C2") (pin "2") (pinfunction "2_2") (pintype "passive"))
      (node (ref "Q1") (pin "1") (pinfunction "1_1") (pintype "passive"))
      (node (ref "U1") (pin "23") (pinfunction "XTAL2_23") (pintype "output"))
    )
    (net (code "83") (name "Net-(U1-~{RESET})") (class "Default")
      (node (ref "R13") (pin "2") (pinfunction "2_2") (pintype "passive"))
      (node (ref "U1") (pin "20") (pinfunction "~{RESET}_20") (pintype "input"))
    )
    (net (code "84") (name "VCC") (class "Default")
      (node (ref "C1") (pin "2") (pinfunction "2_2") (pintype "passive"))
      (node (ref "J1") (pin "14") (pinfunction "14_14") (pintype "passive"))
      (node (ref "P10") (pin "4") (pinfunction "4_4") (pintype "passive"))
      (node (ref "R10") (pin "2") (pinfunction "2_2") (pintype "passive"))
      (node (ref "R11") (pin "2") (pinfunction "2_2") (pintype "passive"))
      (node (ref "R12") (pin "2") (pinfunction "2_2") (pintype "passive"))
      (node (ref "R13") (pin "1") (pinfunction "1_1") (pintype "passive"))
      (node (ref "R9") (pin "2") (pinfunction "2_2") (pintype "passive"))
      (node (ref "U1") (pin "21") (pinfunction "VCC_21") (pintype "power_in"))
      (node (ref "U1") (pin "52") (pinfunction "VCC_52") (pintype "power_in"))
      (node (ref "U1") (pin "64") (pinfunction "AVCC_64") (pintype "power_in"))
    )
    (net (code "85") (name "unconnected-(K1-N.C.-Pad4)") (class "Default")
      (node (ref "K1") (pin "4") (pinfunction "N.C._4") (pintype "passive+no_connect"))
    )
    (net (code "86") (name "unconnected-(K8-N.C.-Pad4)") (class "Default")
      (node (ref "K8") (pin "4") (pinfunction "N.C._4") (pintype "passive+no_connect"))
    )
    (net (code "87") (name "unconnected-(P10-Pad7)") (class "Default")
      (node (ref "P10") (pin "7") (pinfunction "7_7") (pintype "passive+no_connect"))
    )
    (net (code "88") (name "unconnected-(P10-Pad8)") (class "Default")
      (node (ref "P10") (pin "8") (pinfunction "8_8") (pintype "passive+no_connect"))
    )
    (net (code "89") (name "unconnected-(U1-AREF-Pad62)") (class "Default")
      (node (ref "U1") (pin "62") (pinfunction "AREF_62") (pintype "passive+no_connect"))
    )
    (net (code "90") (name "unconnected-(U1-PB5_(OC1A)-Pad15)") (class "Default")
      (node (ref "U1") (pin "15") (pinfunction "PB5_(OC1A)_15") (pintype "bidirectional+no_connect"))
    )
    (net (code "91") (name "unconnected-(U1-PB6_(OC1B)-Pad16)") (class "Default")
      (node (ref "U1") (pin "16") (pinfunction "PB6_(OC1B)_16") (pintype "bidirectional+no_connect"))
    )
    (net (code "92") (name "unconnected-(U1-PB7_(OC2{slash}OC1C)-Pad17)") (class "Default")
      (node (ref "U1") (pin "17") (pinfunction "PB7_(OC2/OC1C)_17") (pintype "bidirectional+no_connect"))
    )
    (net (code "93") (name "unconnected-(U1-PC0_(A8)-Pad35)") (class "Default")
      (node (ref "U1") (pin "35") (pinfunction "PC0_(A8)_35") (pintype "bidirectional+no_connect"))
    )
    (net (code "94") (name "unconnected-(U1-PC1_(A9)-Pad36)") (class "Default")
      (node (ref "U1") (pin "36") (pinfunction "PC1_(A9)_36") (pintype "bidirectional+no_connect"))
    )
    (net (code "95") (name "unconnected-(U1-PC2_(A10-Pad37)") (class "Default")
      (node (ref "U1") (pin "37") (pinfunction "PC2_(A10_37") (pintype "bidirectional+no_connect"))
    )
    (net (code "96") (name "unconnected-(U1-PC3_(A11)-Pad38)") (class "Default")
      (node (ref "U1") (pin "38") (pinfunction "PC3_(A11)_38") (pintype "bidirectional+no_connect"))
    )
    (net (code "97") (name "unconnected-(U1-PD1_(SDA{slash}INT1)-Pad26)") (class "Default")
      (node (ref "U1") (pin "26") (pinfunction "PD1_(SDA/INT1)_26") (pintype "bidirectional+no_connect"))
    )
    (net (code "98") (name "unconnected-(U1-PD6_(T1)-Pad31)") (class "Default")
      (node (ref "U1") (pin "31") (pinfunction "PD6_(T1)_31") (pintype "bidirectional+no_connect"))
    )
    (net (code "99") (name "unconnected-(U1-PE2_(XCK0{slash}AIN0)-Pad4)") (class "Default")
      (node (ref "U1") (pin "4") (pinfunction "PE2_(XCK0/AIN0)_4") (pintype "bidirectional+no_connect"))
    )
    (net (code "100") (name "unconnected-(U1-PE4_(OC3B{slash}INT4)-Pad6)") (class "Default")
      (node (ref "U1") (pin "6") (pinfunction "PE4_(OC3B/INT4)_6") (pintype "bidirectional+no_connect"))
    )
    (net (code "101") (name "unconnected-(U1-PE5_(OC3C{slash}INT5)-Pad7)") (class "Default")
      (node (ref "U1") (pin "7") (pinfunction "PE5_(OC3C/INT5)_7") (pintype "bidirectional+no_connect"))
    )
    (net (code "102") (name "unconnected-(U1-PE6_(T3{slash}INT6)-Pad8)") (class "Default")
      (node (ref "U1") (pin "8") (pinfunction "PE6_(T3/INT6)_8") (pintype "bidirectional+no_connect"))
    )
    (net (code "103") (name "unconnected-(U1-PE7_(IC3{slash}INT7)-Pad9)") (class "Default")
      (node (ref "U1") (pin "9") (pinfunction "PE7_(IC3/INT7)_9") (pintype "bidirectional+no_connect"))
    )
    (net (code "104") (name "unconnected-(U1-PF3_(ADC3)-Pad58)") (class "Default")
      (node (ref "U1") (pin "58") (pinfunction "PF3_(ADC3)_58") (pintype "bidirectional+no_connect"))
    )
    (net (code "105") (name "unconnected-(U1-PG0_(~{WR})-Pad33)") (class "Default")
      (node (ref "U1") (pin "33") (pinfunction "PG0_(~{WR})_33") (pintype "bidirectional+no_connect"))
    )
    (net (code "106") (name "unconnected-(U1-PG1_(~{RD})-Pad34)") (class "Default")
      (node (ref "U1") (pin "34") (pinfunction "PG1_(~{RD})_34") (pintype "bidirectional+no_connect"))
    )
    (net (code "107") (name "unconnected-(U1-PG2_(ALE)-Pad43)") (class "Default")
      (node (ref "U1") (pin "43") (pinfunction "PG2_(ALE)_43") (pintype "bidirectional+no_connect"))
    )
    (net (code "108") (name "unconnected-(U1-PG3{slash}TOSC2-Pad18)") (class "Default")
      (node (ref "U1") (pin "18") (pinfunction "PG3/TOSC2_18") (pintype "bidirectional+no_connect"))
    )
    (net (code "109") (name "unconnected-(U1-PG4{slash}TOSC1-Pad19)") (class "Default")
      (node (ref "U1") (pin "19") (pinfunction "PG4/TOSC1_19") (pintype "bidirectional+no_connect"))
    )
    (net (code "110") (name "unconnected-(U1-~{PEN}-Pad1)") (class "Default")
      (node (ref "U1") (pin "1") (pinfunction "~{PEN}_1") (pintype "input+no_connect"))
    )
  )
)
